# Keypad.net
KiCad netlist of a schematic drawn in Altium Designer
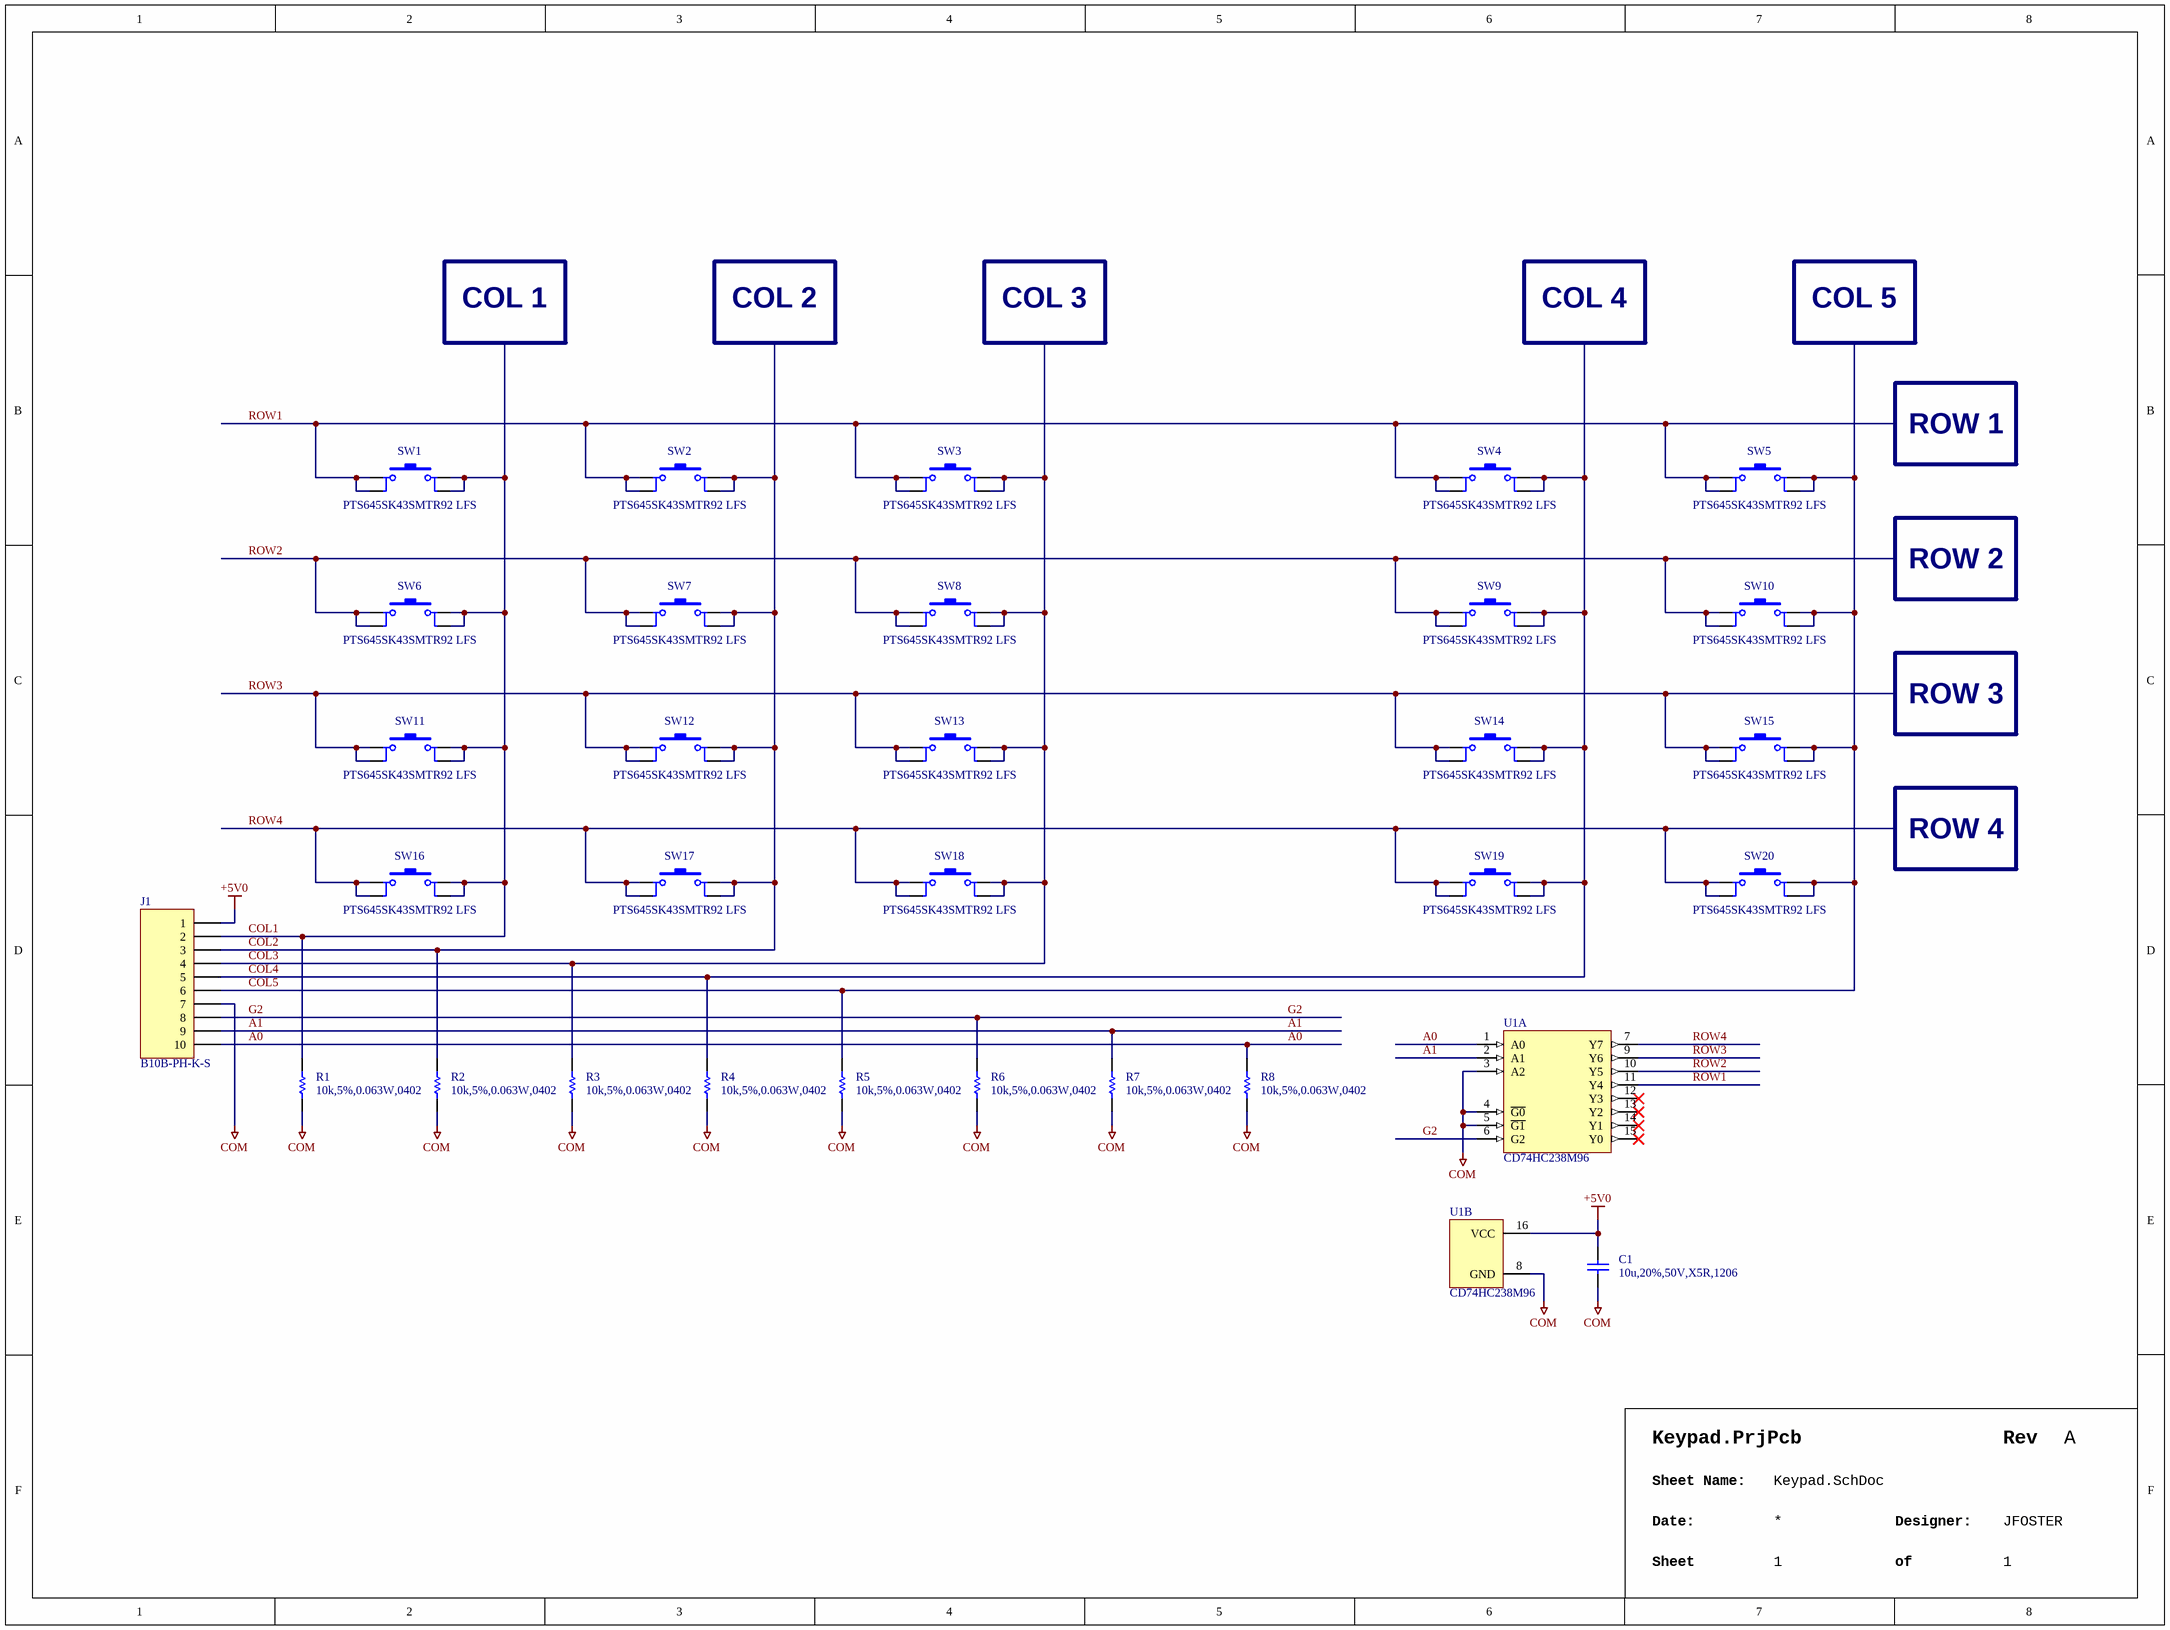
[diagram p0: Keypad.SchDoc]

(export (version "E")
  (design (tool "Eeschema 10.0.6"))
  (components
    (comp (ref "C1")
      (value "10u,20%,50V,X5R,1206")
      (footprint "CAPC3216X16N")
      (description "10ï¿½F ï¿½20% 50V Ceramic Capacitor X5R 1206 (3216 Metric)")
      (fields
        (field (name "MANUFACTURER 1 PART NUMBER") "CL31A106MBHNNNE")
        (field (name "VENDOR 1 PART NUMBER") "1276-6736-1-ND")
        (field (name "CREATEDBY") "Judd Foster")
      )
      (libsource (lib "Component Library") (part "CAP,Cer,10uF,50VDC,X5R,1206"))
    )
    (comp (ref "J1")
      (value "B10B-PH-K-S")
      (footprint "JST_B10B-PH-K-S")
      (description "Connector Header Through Hole 10 position 0.079\" (2.00mm)")
      (fields (field (name "VENDOR 1 PART NUMBER") "455-1712-ND") (field (name "CREATEDBY") "Judd Foster"))
      (libsource (lib "Component Library") (part "CONN,JST,10 Pin,2mm,Vert,Thru"))
    )
    (comp (ref "R1")
      (value "10k,5%,0.063W,0402")
      (footprint "RESC1005X04N")
      (description "10 kOhms ï¿½5% 0.063W, 1/16W Chip Resistor 0402 (1005 Metric) Automotive AEC-Q200 Thick Film")
      (fields
        (field (name "MANUFACTURER 1 PART NUMBER") "RMCF0402JT10K0")
        (field (name "VENDOR 1 PART NUMBER") "RMCF0402JT10K0CT-ND")
        (field (name "CREATEDBY") "Judd Foster")
      )
      (libsource (lib "Component Library") (part "RES,10k,5%,0.063W,0402"))
    )
    (comp (ref "R2")
      (value "10k,5%,0.063W,0402")
      (footprint "RESC1005X04N")
      (description "10 kOhms ï¿½5% 0.063W, 1/16W Chip Resistor 0402 (1005 Metric) Automotive AEC-Q200 Thick Film")
      (fields
        (field (name "MANUFACTURER 1 PART NUMBER") "RMCF0402JT10K0")
        (field (name "VENDOR 1 PART NUMBER") "RMCF0402JT10K0CT-ND")
        (field (name "CREATEDBY") "Judd Foster")
      )
      (libsource (lib "Component Library") (part "RES,10k,5%,0.063W,0402"))
    )
    (comp (ref "R3")
      (value "10k,5%,0.063W,0402")
      (footprint "RESC1005X04N")
      (description "10 kOhms ï¿½5% 0.063W, 1/16W Chip Resistor 0402 (1005 Metric) Automotive AEC-Q200 Thick Film")
      (fields
        (field (name "MANUFACTURER 1 PART NUMBER") "RMCF0402JT10K0")
        (field (name "VENDOR 1 PART NUMBER") "RMCF0402JT10K0CT-ND")
        (field (name "CREATEDBY") "Judd Foster")
      )
      (libsource (lib "Component Library") (part "RES,10k,5%,0.063W,0402"))
    )
    (comp (ref "R4")
      (value "10k,5%,0.063W,0402")
      (footprint "RESC1005X04N")
      (description "10 kOhms ï¿½5% 0.063W, 1/16W Chip Resistor 0402 (1005 Metric) Automotive AEC-Q200 Thick Film")
      (fields
        (field (name "MANUFACTURER 1 PART NUMBER") "RMCF0402JT10K0")
        (field (name "VENDOR 1 PART NUMBER") "RMCF0402JT10K0CT-ND")
        (field (name "CREATEDBY") "Judd Foster")
      )
      (libsource (lib "Component Library") (part "RES,10k,5%,0.063W,0402"))
    )
    (comp (ref "R5")
      (value "10k,5%,0.063W,0402")
      (footprint "RESC1005X04N")
      (description "10 kOhms ï¿½5% 0.063W, 1/16W Chip Resistor 0402 (1005 Metric) Automotive AEC-Q200 Thick Film")
      (fields
        (field (name "MANUFACTURER 1 PART NUMBER") "RMCF0402JT10K0")
        (field (name "VENDOR 1 PART NUMBER") "RMCF0402JT10K0CT-ND")
        (field (name "CREATEDBY") "Judd Foster")
      )
      (libsource (lib "Component Library") (part "RES,10k,5%,0.063W,0402"))
    )
    (comp (ref "R6")
      (value "10k,5%,0.063W,0402")
      (footprint "RESC1005X04N")
      (description "10 kOhms ï¿½5% 0.063W, 1/16W Chip Resistor 0402 (1005 Metric) Automotive AEC-Q200 Thick Film")
      (fields
        (field (name "MANUFACTURER 1 PART NUMBER") "RMCF0402JT10K0")
        (field (name "VENDOR 1 PART NUMBER") "RMCF0402JT10K0CT-ND")
        (field (name "CREATEDBY") "Judd Foster")
      )
      (libsource (lib "Component Library") (part "RES,10k,5%,0.063W,0402"))
    )
    (comp (ref "R7")
      (value "10k,5%,0.063W,0402")
      (footprint "RESC1005X04N")
      (description "10 kOhms ï¿½5% 0.063W, 1/16W Chip Resistor 0402 (1005 Metric) Automotive AEC-Q200 Thick Film")
      (fields
        (field (name "MANUFACTURER 1 PART NUMBER") "RMCF0402JT10K0")
        (field (name "VENDOR 1 PART NUMBER") "RMCF0402JT10K0CT-ND")
        (field (name "CREATEDBY") "Judd Foster")
      )
      (libsource (lib "Component Library") (part "RES,10k,5%,0.063W,0402"))
    )
    (comp (ref "R8")
      (value "10k,5%,0.063W,0402")
      (footprint "RESC1005X04N")
      (description "10 kOhms ï¿½5% 0.063W, 1/16W Chip Resistor 0402 (1005 Metric) Automotive AEC-Q200 Thick Film")
      (fields
        (field (name "MANUFACTURER 1 PART NUMBER") "RMCF0402JT10K0")
        (field (name "VENDOR 1 PART NUMBER") "RMCF0402JT10K0CT-ND")
        (field (name "CREATEDBY") "Judd Foster")
      )
      (libsource (lib "Component Library") (part "RES,10k,5%,0.063W,0402"))
    )
    (comp (ref "SW1")
      (value "PTS645SK43SMTR92 LFS")
      (footprint "C&K_PTS645SK43SMTR92 LFS")
      (description "Tactile Switch SPST-NO Top Actuated Surface Mount")
      (fields (field (name "VENDOR 1 PART NUMBER") "CKN9084CT-ND") (field (name "CREATEDBY") "Judd Foster"))
      (libsource (lib "Component Library") (part "Switch,Tactile,SPST-NO,SMD,H4.3"))
    )
    (comp (ref "SW2")
      (value "PTS645SK43SMTR92 LFS")
      (footprint "C&K_PTS645SK43SMTR92 LFS")
      (description "Tactile Switch SPST-NO Top Actuated Surface Mount")
      (fields (field (name "VENDOR 1 PART NUMBER") "CKN9084CT-ND") (field (name "CREATEDBY") "Judd Foster"))
      (libsource (lib "Component Library") (part "Switch,Tactile,SPST-NO,SMD,H4.3"))
    )
    (comp (ref "SW3")
      (value "PTS645SK43SMTR92 LFS")
      (footprint "C&K_PTS645SK43SMTR92 LFS")
      (description "Tactile Switch SPST-NO Top Actuated Surface Mount")
      (fields (field (name "VENDOR 1 PART NUMBER") "CKN9084CT-ND") (field (name "CREATEDBY") "Judd Foster"))
      (libsource (lib "Component Library") (part "Switch,Tactile,SPST-NO,SMD,H4.3"))
    )
    (comp (ref "SW4")
      (value "PTS645SK43SMTR92 LFS")
      (footprint "C&K_PTS645SK43SMTR92 LFS")
      (description "Tactile Switch SPST-NO Top Actuated Surface Mount")
      (fields (field (name "VENDOR 1 PART NUMBER") "CKN9084CT-ND") (field (name "CREATEDBY") "Judd Foster"))
      (libsource (lib "Component Library") (part "Switch,Tactile,SPST-NO,SMD,H4.3"))
    )
    (comp (ref "SW5")
      (value "PTS645SK43SMTR92 LFS")
      (footprint "C&K_PTS645SK43SMTR92 LFS")
      (description "Tactile Switch SPST-NO Top Actuated Surface Mount")
      (fields (field (name "VENDOR 1 PART NUMBER") "CKN9084CT-ND") (field (name "CREATEDBY") "Judd Foster"))
      (libsource (lib "Component Library") (part "Switch,Tactile,SPST-NO,SMD,H4.3"))
    )
    (comp (ref "SW6")
      (value "PTS645SK43SMTR92 LFS")
      (footprint "C&K_PTS645SK43SMTR92 LFS")
      (description "Tactile Switch SPST-NO Top Actuated Surface Mount")
      (fields (field (name "VENDOR 1 PART NUMBER") "CKN9084CT-ND") (field (name "CREATEDBY") "Judd Foster"))
      (libsource (lib "Component Library") (part "Switch,Tactile,SPST-NO,SMD,H4.3"))
    )
    (comp (ref "SW7")
      (value "PTS645SK43SMTR92 LFS")
      (footprint "C&K_PTS645SK43SMTR92 LFS")
      (description "Tactile Switch SPST-NO Top Actuated Surface Mount")
      (fields (field (name "VENDOR 1 PART NUMBER") "CKN9084CT-ND") (field (name "CREATEDBY") "Judd Foster"))
      (libsource (lib "Component Library") (part "Switch,Tactile,SPST-NO,SMD,H4.3"))
    )
    (comp (ref "SW8")
      (value "PTS645SK43SMTR92 LFS")
      (footprint "C&K_PTS645SK43SMTR92 LFS")
      (description "Tactile Switch SPST-NO Top Actuated Surface Mount")
      (fields (field (name "VENDOR 1 PART NUMBER") "CKN9084CT-ND") (field (name "CREATEDBY") "Judd Foster"))
      (libsource (lib "Component Library") (part "Switch,Tactile,SPST-NO,SMD,H4.3"))
    )
    (comp (ref "SW9")
      (value "PTS645SK43SMTR92 LFS")
      (footprint "C&K_PTS645SK43SMTR92 LFS")
      (description "Tactile Switch SPST-NO Top Actuated Surface Mount")
      (fields (field (name "VENDOR 1 PART NUMBER") "CKN9084CT-ND") (field (name "CREATEDBY") "Judd Foster"))
      (libsource (lib "Component Library") (part "Switch,Tactile,SPST-NO,SMD,H4.3"))
    )
    (comp (ref "SW10")
      (value "PTS645SK43SMTR92 LFS")
      (footprint "C&K_PTS645SK43SMTR92 LFS")
      (description "Tactile Switch SPST-NO Top Actuated Surface Mount")
      (fields (field (name "VENDOR 1 PART NUMBER") "CKN9084CT-ND") (field (name "CREATEDBY") "Judd Foster"))
      (libsource (lib "Component Library") (part "Switch,Tactile,SPST-NO,SMD,H4.3"))
    )
    (comp (ref "SW11")
      (value "PTS645SK43SMTR92 LFS")
      (footprint "C&K_PTS645SK43SMTR92 LFS")
      (description "Tactile Switch SPST-NO Top Actuated Surface Mount")
      (fields (field (name "VENDOR 1 PART NUMBER") "CKN9084CT-ND") (field (name "CREATEDBY") "Judd Foster"))
      (libsource (lib "Component Library") (part "Switch,Tactile,SPST-NO,SMD,H4.3"))
    )
    (comp (ref "SW12")
      (value "PTS645SK43SMTR92 LFS")
      (footprint "C&K_PTS645SK43SMTR92 LFS")
      (description "Tactile Switch SPST-NO Top Actuated Surface Mount")
      (fields (field (name "VENDOR 1 PART NUMBER") "CKN9084CT-ND") (field (name "CREATEDBY") "Judd Foster"))
      (libsource (lib "Component Library") (part "Switch,Tactile,SPST-NO,SMD,H4.3"))
    )
    (comp (ref "SW13")
      (value "PTS645SK43SMTR92 LFS")
      (footprint "C&K_PTS645SK43SMTR92 LFS")
      (description "Tactile Switch SPST-NO Top Actuated Surface Mount")
      (fields (field (name "VENDOR 1 PART NUMBER") "CKN9084CT-ND") (field (name "CREATEDBY") "Judd Foster"))
      (libsource (lib "Component Library") (part "Switch,Tactile,SPST-NO,SMD,H4.3"))
    )
    (comp (ref "SW14")
      (value "PTS645SK43SMTR92 LFS")
      (footprint "C&K_PTS645SK43SMTR92 LFS")
      (description "Tactile Switch SPST-NO Top Actuated Surface Mount")
      (fields (field (name "VENDOR 1 PART NUMBER") "CKN9084CT-ND") (field (name "CREATEDBY") "Judd Foster"))
      (libsource (lib "Component Library") (part "Switch,Tactile,SPST-NO,SMD,H4.3"))
    )
    (comp (ref "SW15")
      (value "PTS645SK43SMTR92 LFS")
      (footprint "C&K_PTS645SK43SMTR92 LFS")
      (description "Tactile Switch SPST-NO Top Actuated Surface Mount")
      (fields (field (name "VENDOR 1 PART NUMBER") "CKN9084CT-ND") (field (name "CREATEDBY") "Judd Foster"))
      (libsource (lib "Component Library") (part "Switch,Tactile,SPST-NO,SMD,H4.3"))
    )
    (comp (ref "SW16")
      (value "PTS645SK43SMTR92 LFS")
      (footprint "C&K_PTS645SK43SMTR92 LFS")
      (description "Tactile Switch SPST-NO Top Actuated Surface Mount")
      (fields (field (name "VENDOR 1 PART NUMBER") "CKN9084CT-ND") (field (name "CREATEDBY") "Judd Foster"))
      (libsource (lib "Component Library") (part "Switch,Tactile,SPST-NO,SMD,H4.3"))
    )
    (comp (ref "SW17")
      (value "PTS645SK43SMTR92 LFS")
      (footprint "C&K_PTS645SK43SMTR92 LFS")
      (description "Tactile Switch SPST-NO Top Actuated Surface Mount")
      (fields (field (name "VENDOR 1 PART NUMBER") "CKN9084CT-ND") (field (name "CREATEDBY") "Judd Foster"))
      (libsource (lib "Component Library") (part "Switch,Tactile,SPST-NO,SMD,H4.3"))
    )
    (comp (ref "SW18")
      (value "PTS645SK43SMTR92 LFS")
      (footprint "C&K_PTS645SK43SMTR92 LFS")
      (description "Tactile Switch SPST-NO Top Actuated Surface Mount")
      (fields (field (name "VENDOR 1 PART NUMBER") "CKN9084CT-ND") (field (name "CREATEDBY") "Judd Foster"))
      (libsource (lib "Component Library") (part "Switch,Tactile,SPST-NO,SMD,H4.3"))
    )
    (comp (ref "SW19")
      (value "PTS645SK43SMTR92 LFS")
      (footprint "C&K_PTS645SK43SMTR92 LFS")
      (description "Tactile Switch SPST-NO Top Actuated Surface Mount")
      (fields (field (name "VENDOR 1 PART NUMBER") "CKN9084CT-ND") (field (name "CREATEDBY") "Judd Foster"))
      (libsource (lib "Component Library") (part "Switch,Tactile,SPST-NO,SMD,H4.3"))
    )
    (comp (ref "SW20")
      (value "PTS645SK43SMTR92 LFS")
      (footprint "C&K_PTS645SK43SMTR92 LFS")
      (description "Tactile Switch SPST-NO Top Actuated Surface Mount")
      (fields (field (name "VENDOR 1 PART NUMBER") "CKN9084CT-ND") (field (name "CREATEDBY") "Judd Foster"))
      (libsource (lib "Component Library") (part "Switch,Tactile,SPST-NO,SMD,H4.3"))
    )
    (comp (ref "U1")
      (value "CD74HC238M96")
      (footprint "TEXASINSTRUMENTS_PKG_NS0016A")
      (description "Decoder/Demultiplexer 1 x 3:8 16-SOIC")
      (fields (field (name "VENDOR 1 PART NUMBER") "296-24353-1-ND") (field (name "CREATEDBY") "Judd Foster"))
      (libsource (lib "") (part "CD74HC238M96_1"))
    )
  )
  (nets
    (net (code "1") (name "+5V0") (class "Default")
      (node (ref "C1") (pin "2") (pinfunction "2_2") (pintype "passive"))
      (node (ref "J1") (pin "1") (pinfunction "1_1") (pintype "passive"))
      (node (ref "U1") (pin "16") (pinfunction "VCC_16") (pintype "power_in"))
    )
    (net (code "2") (name "/A0") (class "Default")
      (node (ref "J1") (pin "10") (pinfunction "10_10") (pintype "passive"))
      (node (ref "R8") (pin "2") (pinfunction "2_2") (pintype "passive"))
      (node (ref "U1") (pin "1") (pinfunction "A0_1") (pintype "input"))
    )
    (net (code "3") (name "/A1") (class "Default")
      (node (ref "J1") (pin "9") (pinfunction "9_9") (pintype "passive"))
      (node (ref "R7") (pin "2") (pinfunction "2_2") (pintype "passive"))
      (node (ref "U1") (pin "2") (pinfunction "A1_2") (pintype "input"))
    )
    (net (code "4") (name "/COL1") (class "Default")
      (node (ref "J1") (pin "2") (pinfunction "2_2") (pintype "passive"))
      (node (ref "R1") (pin "2") (pinfunction "2_2") (pintype "passive"))
      (node (ref "SW1") (pin "3") (pinfunction "3_3") (pintype "passive"))
      (node (ref "SW1") (pin "4") (pinfunction "4_4") (pintype "passive"))
      (node (ref "SW11") (pin "3") (pinfunction "3_3") (pintype "passive"))
      (node (ref "SW11") (pin "4") (pinfunction "4_4") (pintype "passive"))
      (node (ref "SW16") (pin "3") (pinfunction "3_3") (pintype "passive"))
      (node (ref "SW16") (pin "4") (pinfunction "4_4") (pintype "passive"))
      (node (ref "SW6") (pin "3") (pinfunction "3_3") (pintype "passive"))
      (node (ref "SW6") (pin "4") (pinfunction "4_4") (pintype "passive"))
    )
    (net (code "5") (name "/COL2") (class "Default")
      (node (ref "J1") (pin "3") (pinfunction "3_3") (pintype "passive"))
      (node (ref "R2") (pin "2") (pinfunction "2_2") (pintype "passive"))
      (node (ref "SW12") (pin "3") (pinfunction "3_3") (pintype "passive"))
      (node (ref "SW12") (pin "4") (pinfunction "4_4") (pintype "passive"))
      (node (ref "SW17") (pin "3") (pinfunction "3_3") (pintype "passive"))
      (node (ref "SW17") (pin "4") (pinfunction "4_4") (pintype "passive"))
      (node (ref "SW2") (pin "3") (pinfunction "3_3") (pintype "passive"))
      (node (ref "SW2") (pin "4") (pinfunction "4_4") (pintype "passive"))
      (node (ref "SW7") (pin "3") (pinfunction "3_3") (pintype "passive"))
      (node (ref "SW7") (pin "4") (pinfunction "4_4") (pintype "passive"))
    )
    (net (code "6") (name "/COL3") (class "Default")
      (node (ref "J1") (pin "4") (pinfunction "4_4") (pintype "passive"))
      (node (ref "R3") (pin "2") (pinfunction "2_2") (pintype "passive"))
      (node (ref "SW13") (pin "3") (pinfunction "3_3") (pintype "passive"))
      (node (ref "SW13") (pin "4") (pinfunction "4_4") (pintype "passive"))
      (node (ref "SW18") (pin "3") (pinfunction "3_3") (pintype "passive"))
      (node (ref "SW18") (pin "4") (pinfunction "4_4") (pintype "passive"))
      (node (ref "SW3") (pin "3") (pinfunction "3_3") (pintype "passive"))
      (node (ref "SW3") (pin "4") (pinfunction "4_4") (pintype "passive"))
      (node (ref "SW8") (pin "3") (pinfunction "3_3") (pintype "passive"))
      (node (ref "SW8") (pin "4") (pinfunction "4_4") (pintype "passive"))
    )
    (net (code "7") (name "/COL4") (class "Default")
      (node (ref "J1") (pin "5") (pinfunction "5_5") (pintype "passive"))
      (node (ref "R4") (pin "2") (pinfunction "2_2") (pintype "passive"))
      (node (ref "SW14") (pin "3") (pinfunction "3_3") (pintype "passive"))
      (node (ref "SW14") (pin "4") (pinfunction "4_4") (pintype "passive"))
      (node (ref "SW19") (pin "3") (pinfunction "3_3") (pintype "passive"))
      (node (ref "SW19") (pin "4") (pinfunction "4_4") (pintype "passive"))
      (node (ref "SW4") (pin "3") (pinfunction "3_3") (pintype "passive"))
      (node (ref "SW4") (pin "4") (pinfunction "4_4") (pintype "passive"))
      (node (ref "SW9") (pin "3") (pinfunction "3_3") (pintype "passive"))
      (node (ref "SW9") (pin "4") (pinfunction "4_4") (pintype "passive"))
    )
    (net (code "8") (name "/COL5") (class "Default")
      (node (ref "J1") (pin "6") (pinfunction "6_6") (pintype "passive"))
      (node (ref "R5") (pin "2") (pinfunction "2_2") (pintype "passive"))
      (node (ref "SW10") (pin "3") (pinfunction "3_3") (pintype "passive"))
      (node (ref "SW10") (pin "4") (pinfunction "4_4") (pintype "passive"))
      (node (ref "SW15") (pin "3") (pinfunction "3_3") (pintype "passive"))
      (node (ref "SW15") (pin "4") (pinfunction "4_4") (pintype "passive"))
      (node (ref "SW20") (pin "3") (pinfunction "3_3") (pintype "passive"))
      (node (ref "SW20") (pin "4") (pinfunction "4_4") (pintype "passive"))
      (node (ref "SW5") (pin "3") (pinfunction "3_3") (pintype "passive"))
      (node (ref "SW5") (pin "4") (pinfunction "4_4") (pintype "passive"))
    )
    (net (code "9") (name "/G2") (class "Default")
      (node (ref "J1") (pin "8") (pinfunction "8_8") (pintype "passive"))
      (node (ref "R6") (pin "2") (pinfunction "2_2") (pintype "passive"))
      (node (ref "U1") (pin "6") (pinfunction "G2_6") (pintype "input"))
    )
    (net (code "10") (name "/ROW1") (class "Default")
      (node (ref "SW1") (pin "1") (pinfunction "1_1") (pintype "passive"))
      (node (ref "SW1") (pin "2") (pinfunction "2_2") (pintype "passive"))
      (node (ref "SW2") (pin "1") (pinfunction "1_1") (pintype "passive"))
      (node (ref "SW2") (pin "2") (pinfunction "2_2") (pintype "passive"))
      (node (ref "SW3") (pin "1") (pinfunction "1_1") (pintype "passive"))
      (node (ref "SW3") (pin "2") (pinfunction "2_2") (pintype "passive"))
      (node (ref "SW4") (pin "1") (pinfunction "1_1") (pintype "passive"))
      (node (ref "SW4") (pin "2") (pinfunction "2_2") (pintype "passive"))
      (node (ref "SW5") (pin "1") (pinfunction "1_1") (pintype "passive"))
      (node (ref "SW5") (pin "2") (pinfunction "2_2") (pintype "passive"))
      (node (ref "U1") (pin "11") (pinfunction "Y4_11") (pintype "output"))
    )
    (net (code "11") (name "/ROW2") (class "Default")
      (node (ref "SW10") (pin "1") (pinfunction "1_1") (pintype "passive"))
      (node (ref "SW10") (pin "2") (pinfunction "2_2") (pintype "passive"))
      (node (ref "SW6") (pin "1") (pinfunction "1_1") (pintype "passive"))
      (node (ref "SW6") (pin "2") (pinfunction "2_2") (pintype "passive"))
      (node (ref "SW7") (pin "1") (pinfunction "1_1") (pintype "passive"))
      (node (ref "SW7") (pin "2") (pinfunction "2_2") (pintype "passive"))
      (node (ref "SW8") (pin "1") (pinfunction "1_1") (pintype "passive"))
      (node (ref "SW8") (pin "2") (pinfunction "2_2") (pintype "passive"))
      (node (ref "SW9") (pin "1") (pinfunction "1_1") (pintype "passive"))
      (node (ref "SW9") (pin "2") (pinfunction "2_2") (pintype "passive"))
      (node (ref "U1") (pin "10") (pinfunction "Y5_10") (pintype "output"))
    )
    (net (code "12") (name "/ROW3") (class "Default")
      (node (ref "SW11") (pin "1") (pinfunction "1_1") (pintype "passive"))
      (node (ref "SW11") (pin "2") (pinfunction "2_2") (pintype "passive"))
      (node (ref "SW12") (pin "1") (pinfunction "1_1") (pintype "passive"))
      (node (ref "SW12") (pin "2") (pinfunction "2_2") (pintype "passive"))
      (node (ref "SW13") (pin "1") (pinfunction "1_1") (pintype "passive"))
      (node (ref "SW13") (pin "2") (pinfunction "2_2") (pintype "passive"))
      (node (ref "SW14") (pin "1") (pinfunction "1_1") (pintype "passive"))
      (node (ref "SW14") (pin "2") (pinfunction "2_2") (pintype "passive"))
      (node (ref "SW15") (pin "1") (pinfunction "1_1") (pintype "passive"))
      (node (ref "SW15") (pin "2") (pinfunction "2_2") (pintype "passive"))
      (node (ref "U1") (pin "9") (pinfunction "Y6_9") (pintype "output"))
    )
    (net (code "13") (name "/ROW4") (class "Default")
      (node (ref "SW16") (pin "1") (pinfunction "1_1") (pintype "passive"))
      (node (ref "SW16") (pin "2") (pinfunction "2_2") (pintype "passive"))
      (node (ref "SW17") (pin "1") (pinfunction "1_1") (pintype "passive"))
      (node (ref "SW17") (pin "2") (pinfunction "2_2") (pintype "passive"))
      (node (ref "SW18") (pin "1") (pinfunction "1_1") (pintype "passive"))
      (node (ref "SW18") (pin "2") (pinfunction "2_2") (pintype "passive"))
      (node (ref "SW19") (pin "1") (pinfunction "1_1") (pintype "passive"))
      (node (ref "SW19") (pin "2") (pinfunction "2_2") (pintype "passive"))
      (node (ref "SW20") (pin "1") (pinfunction "1_1") (pintype "passive"))
      (node (ref "SW20") (pin "2") (pinfunction "2_2") (pintype "passive"))
      (node (ref "U1") (pin "7") (pinfunction "Y7_7") (pintype "output"))
    )
    (net (code "14") (name "COM") (class "Default")
      (node (ref "C1") (pin "1") (pinfunction "1_1") (pintype "passive"))
      (node (ref "J1") (pin "7") (pinfunction "7_7") (pintype "passive"))
      (node (ref "R1") (pin "1") (pinfunction "1_1") (pintype "passive"))
      (node (ref "R2") (pin "1") (pinfunction "1_1") (pintype "passive"))
      (node (ref "R3") (pin "1") (pinfunction "1_1") (pintype "passive"))
      (node (ref "R4") (pin "1") (pinfunction "1_1") (pintype "passive"))
      (node (ref "R5") (pin "1") (pinfunction "1_1") (pintype "passive"))
      (node (ref "R6") (pin "1") (pinfunction "1_1") (pintype "passive"))
      (node (ref "R7") (pin "1") (pinfunction "1_1") (pintype "passive"))
      (node (ref "R8") (pin "1") (pinfunction "1_1") (pintype "passive"))
      (node (ref "U1") (pin "3") (pinfunction "A2_3") (pintype "input"))
      (node (ref "U1") (pin "4") (pinfunction "~{G0}_4") (pintype "input"))
      (node (ref "U1") (pin "5") (pinfunction "~{G1}_5") (pintype "input"))
      (node (ref "U1") (pin "8") (pinfunction "GND_8") (pintype "power_in"))
    )
    (net (code "15") (name "unconnected-(U1A-Y0-Pad15)") (class "Default")
      (node (ref "U1") (pin "15") (pinfunction "Y0_15") (pintype "output+no_connect"))
    )
    (net (code "16") (name "unconnected-(U1A-Y1-Pad14)") (class "Default")
      (node (ref "U1") (pin "14") (pinfunction "Y1_14") (pintype "output+no_connect"))
    )
    (net (code "17") (name "unconnected-(U1A-Y2-Pad13)") (class "Default")
      (node (ref "U1") (pin "13") (pinfunction "Y2_13") (pintype "output+no_connect"))
    )
    (net (code "18") (name "unconnected-(U1A-Y3-Pad12)") (class "Default")
      (node (ref "U1") (pin "12") (pinfunction "Y3_12") (pintype "output+no_connect"))
    )
  )
)
